# 5_Motors.net
KiCad netlist of a schematic drawn in Altium Designer
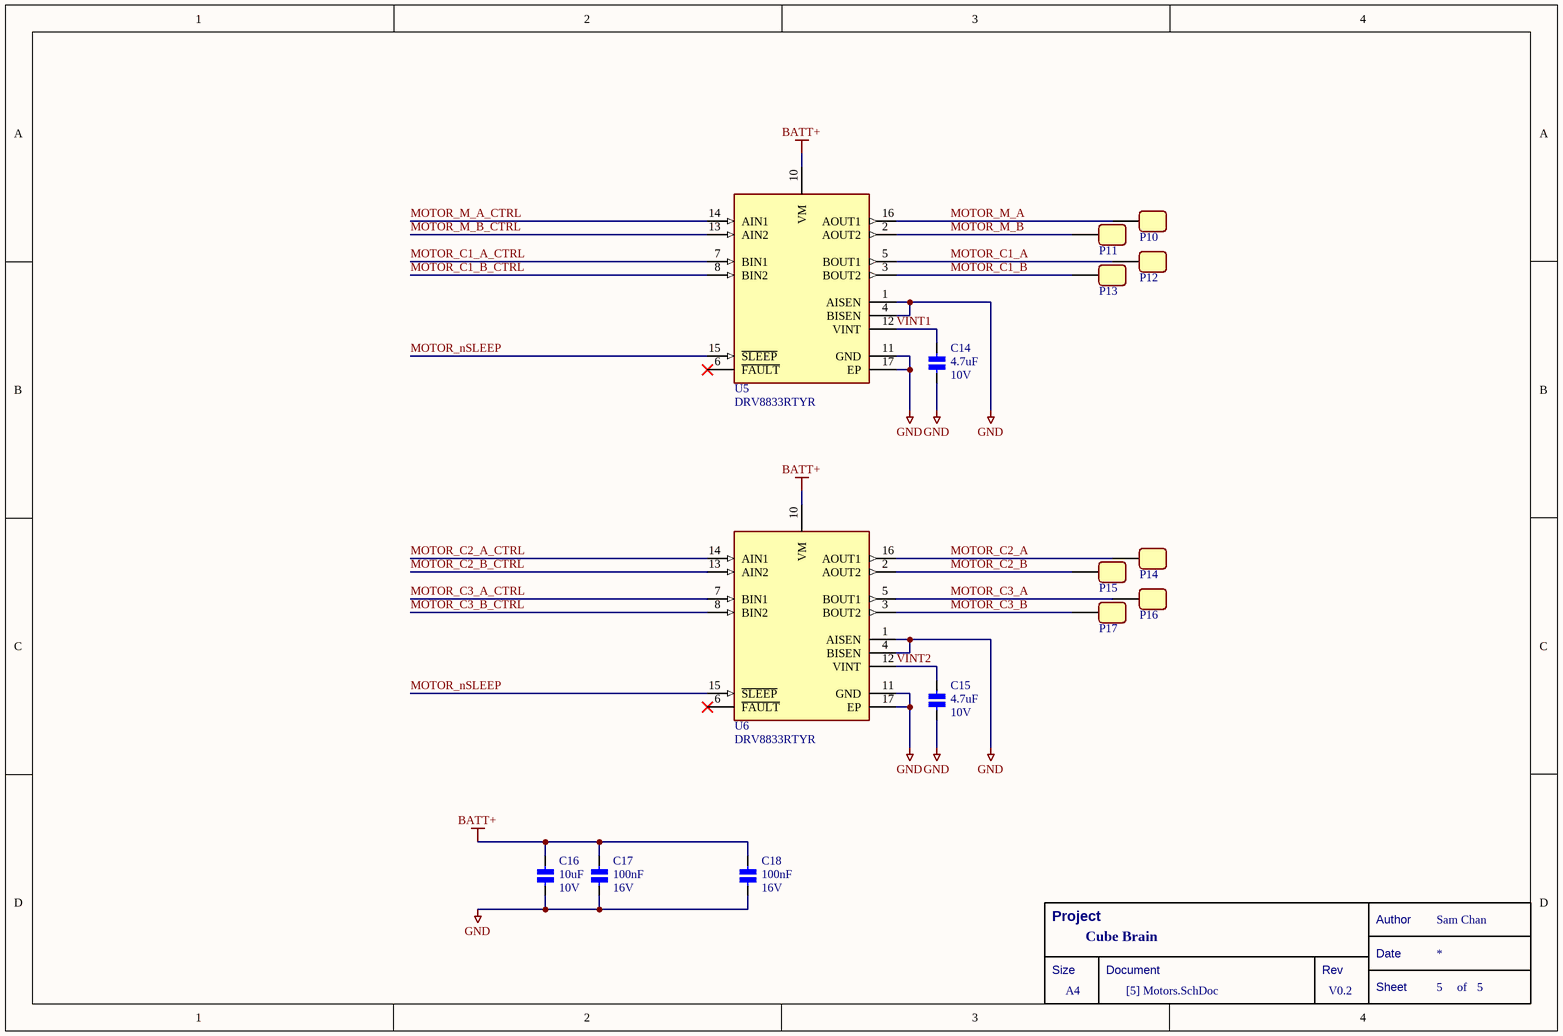
[diagram p0: [5] Motors.SchDoc]

(export (version "E")
  (design (tool "Eeschema 10.0.6"))
  (components
    (comp (ref "C14")
      (value "4.7uF")
      (footprint "CAPC0402X05N")
      (description "CAP CER 4.7UF 10V X5R 0402")
      (fields
        (field (name "MANUFACTURER") "Samsung Electro-Mechanics")
        (field (name "MANUFACTURER PART NUMBER") "CL05A475MP5NRNC")
        (field (name "CAPACITANCE") "4.7uF")
        (field (name "VOLTAGE - RATED") "10V")
      )
      (libsource (lib "Cube Library") (part "CER 4.7UF 10V"))
    )
    (comp (ref "C15")
      (value "4.7uF")
      (footprint "CAPC0402X05N")
      (description "CAP CER 4.7UF 10V X5R 0402")
      (fields
        (field (name "MANUFACTURER") "Samsung Electro-Mechanics")
        (field (name "MANUFACTURER PART NUMBER") "CL05A475MP5NRNC")
        (field (name "CAPACITANCE") "4.7uF")
        (field (name "VOLTAGE - RATED") "10V")
      )
      (libsource (lib "Cube Library") (part "CER 4.7UF 10V"))
    )
    (comp (ref "C16")
      (value "10uF")
      (footprint "CAPC0402X05N")
      (description "CAP CER 10UF 10V X5R 0402")
      (fields
        (field (name "MANUFACTURER") "Murata Electronics")
        (field (name "MANUFACTURER PART NUMBER") "GRM155R61A106ME44D")
        (field (name "CAPACITANCE") "10uF")
        (field (name "VOLTAGE - RATED") "10V")
      )
      (libsource (lib "Cube Library") (part "CER 10UF 10V"))
    )
    (comp (ref "C17")
      (value "100nF")
      (footprint "CAPC0402X05N")
      (description "CAP CER 0.1UF 16V X7R 0402")
      (fields
        (field (name "MANUFACTURER") "Samsung Electro-Mechanics")
        (field (name "MANUFACTURER PART NUMBER") "CL05B104KO5NNNC")
        (field (name "CAPACITANCE") "100nF")
        (field (name "VOLTAGE - RATED") "16V")
      )
      (libsource (lib "Cube Library") (part "CER 100NF 16V"))
    )
    (comp (ref "C18")
      (value "100nF")
      (footprint "CAPC0402X05N")
      (description "CAP CER 0.1UF 16V X7R 0402")
      (fields
        (field (name "MANUFACTURER") "Samsung Electro-Mechanics")
        (field (name "MANUFACTURER PART NUMBER") "CL05B104KO5NNNC")
        (field (name "CAPACITANCE") "100nF")
        (field (name "VOLTAGE - RATED") "16V")
      )
      (libsource (lib "Cube Library") (part "CER 100NF 16V"))
    )
    (comp (ref "P10")
      (value "PAD_4")
      (footprint "PAD_B2B")
      (description "a Pad for board to board connection")
      (libsource (lib "Cube Library") (part "PAD_4"))
    )
    (comp (ref "P11")
      (value "PAD_4")
      (footprint "PAD_B2B")
      (description "a Pad for board to board connection")
      (libsource (lib "Cube Library") (part "PAD_4"))
    )
    (comp (ref "P12")
      (value "PAD_4")
      (footprint "PAD_B2B")
      (description "a Pad for board to board connection")
      (libsource (lib "Cube Library") (part "PAD_4"))
    )
    (comp (ref "P13")
      (value "PAD_4")
      (footprint "PAD_B2B")
      (description "a Pad for board to board connection")
      (libsource (lib "Cube Library") (part "PAD_4"))
    )
    (comp (ref "P14")
      (value "PAD_4")
      (footprint "PAD_B2B")
      (description "a Pad for board to board connection")
      (libsource (lib "Cube Library") (part "PAD_4"))
    )
    (comp (ref "P15")
      (value "PAD_4")
      (footprint "PAD_B2B")
      (description "a Pad for board to board connection")
      (libsource (lib "Cube Library") (part "PAD_4"))
    )
    (comp (ref "P16")
      (value "PAD_4")
      (footprint "PAD_B2B")
      (description "a Pad for board to board connection")
      (libsource (lib "Cube Library") (part "PAD_4"))
    )
    (comp (ref "P17")
      (value "PAD_4")
      (footprint "PAD_B2B")
      (description "a Pad for board to board connection")
      (libsource (lib "Cube Library") (part "PAD_4"))
    )
    (comp (ref "U5")
      (value "DRV8833RTYR")
      (footprint "DRV8833CRTER")
      (description "IC MOTOR DRIVER")
      (fields (field (name "MANUFACTURER") "Texas Instruments"))
      (libsource (lib "Cube Library") (part "DRV8833RTYR"))
    )
    (comp (ref "U6")
      (value "DRV8833RTYR")
      (footprint "DRV8833CRTER")
      (description "IC MOTOR DRIVER")
      (fields (field (name "MANUFACTURER") "Texas Instruments"))
      (libsource (lib "Cube Library") (part "DRV8833RTYR"))
    )
  )
  (nets
    (net (code "1") (name "/MOTOR_C1_A") (class "Default")
      (node (ref "P12") (pin "1") (pinfunction "1_1") (pintype "passive"))
      (node (ref "U5") (pin "5") (pinfunction "BOUT1_5") (pintype "output"))
    )
    (net (code "2") (name "/MOTOR_C1_A_CTRL") (class "Default")
      (node (ref "U5") (pin "7") (pinfunction "BIN1_7") (pintype "input"))
    )
    (net (code "3") (name "/MOTOR_C1_B") (class "Default")
      (node (ref "P13") (pin "1") (pinfunction "1_1") (pintype "passive"))
      (node (ref "U5") (pin "3") (pinfunction "BOUT2_3") (pintype "output"))
    )
    (net (code "4") (name "/MOTOR_C1_B_CTRL") (class "Default")
      (node (ref "U5") (pin "8") (pinfunction "BIN2_8") (pintype "input"))
    )
    (net (code "5") (name "/MOTOR_C2_A") (class "Default")
      (node (ref "P14") (pin "1") (pinfunction "1_1") (pintype "passive"))
      (node (ref "U6") (pin "16") (pinfunction "AOUT1_16") (pintype "output"))
    )
    (net (code "6") (name "/MOTOR_C2_A_CTRL") (class "Default")
      (node (ref "U6") (pin "14") (pinfunction "AIN1_14") (pintype "input"))
    )
    (net (code "7") (name "/MOTOR_C2_B") (class "Default")
      (node (ref "P15") (pin "1") (pinfunction "1_1") (pintype "passive"))
      (node (ref "U6") (pin "2") (pinfunction "AOUT2_2") (pintype "output"))
    )
    (net (code "8") (name "/MOTOR_C2_B_CTRL") (class "Default")
      (node (ref "U6") (pin "13") (pinfunction "AIN2_13") (pintype "input"))
    )
    (net (code "9") (name "/MOTOR_C3_A") (class "Default")
      (node (ref "P16") (pin "1") (pinfunction "1_1") (pintype "passive"))
      (node (ref "U6") (pin "5") (pinfunction "BOUT1_5") (pintype "output"))
    )
    (net (code "10") (name "/MOTOR_C3_A_CTRL") (class "Default")
      (node (ref "U6") (pin "7") (pinfunction "BIN1_7") (pintype "input"))
    )
    (net (code "11") (name "/MOTOR_C3_B") (class "Default")
      (node (ref "P17") (pin "1") (pinfunction "1_1") (pintype "passive"))
      (node (ref "U6") (pin "3") (pinfunction "BOUT2_3") (pintype "output"))
    )
    (net (code "12") (name "/MOTOR_C3_B_CTRL") (class "Default")
      (node (ref "U6") (pin "8") (pinfunction "BIN2_8") (pintype "input"))
    )
    (net (code "13") (name "/MOTOR_M_A") (class "Default")
      (node (ref "P10") (pin "1") (pinfunction "1_1") (pintype "passive"))
      (node (ref "U5") (pin "16") (pinfunction "AOUT1_16") (pintype "output"))
    )
    (net (code "14") (name "/MOTOR_M_A_CTRL") (class "Default")
      (node (ref "U5") (pin "14") (pinfunction "AIN1_14") (pintype "input"))
    )
    (net (code "15") (name "/MOTOR_M_B") (class "Default")
      (node (ref "P11") (pin "1") (pinfunction "1_1") (pintype "passive"))
      (node (ref "U5") (pin "2") (pinfunction "AOUT2_2") (pintype "output"))
    )
    (net (code "16") (name "/MOTOR_M_B_CTRL") (class "Default")
      (node (ref "U5") (pin "13") (pinfunction "AIN2_13") (pintype "input"))
    )
    (net (code "17") (name "/MOTOR_nSLEEP") (class "Default")
      (node (ref "U5") (pin "15") (pinfunction "~{SLEEP}_15") (pintype "input"))
      (node (ref "U6") (pin "15") (pinfunction "~{SLEEP}_15") (pintype "input"))
    )
    (net (code "18") (name "/VINT1") (class "Default")
      (node (ref "C14") (pin "1") (pinfunction "1_1") (pintype "passive"))
      (node (ref "U5") (pin "12") (pinfunction "VINT_12") (pintype "power_in"))
    )
    (net (code "19") (name "/VINT2") (class "Default")
      (node (ref "C15") (pin "1") (pinfunction "1_1") (pintype "passive"))
      (node (ref "U6") (pin "12") (pinfunction "VINT_12") (pintype "power_in"))
    )
    (net (code "20") (name "BATT+") (class "Default")
      (node (ref "C16") (pin "1") (pinfunction "1_1") (pintype "passive"))
      (node (ref "C17") (pin "1") (pinfunction "1_1") (pintype "passive"))
      (node (ref "C18") (pin "1") (pinfunction "1_1") (pintype "passive"))
      (node (ref "U5") (pin "10") (pinfunction "VM_10") (pintype "power_in"))
      (node (ref "U6") (pin "10") (pinfunction "VM_10") (pintype "power_in"))
    )
    (net (code "21") (name "GND") (class "Default")
      (node (ref "C14") (pin "2") (pinfunction "2_2") (pintype "passive"))
      (node (ref "C15") (pin "2") (pinfunction "2_2") (pintype "passive"))
      (node (ref "C16") (pin "2") (pinfunction "2_2") (pintype "passive"))
      (node (ref "C17") (pin "2") (pinfunction "2_2") (pintype "passive"))
      (node (ref "C18") (pin "2") (pinfunction "2_2") (pintype "passive"))
      (node (ref "U5") (pin "1") (pinfunction "AISEN_1") (pintype "passive"))
      (node (ref "U5") (pin "11") (pinfunction "GND_11") (pintype "power_in"))
      (node (ref "U5") (pin "17") (pinfunction "EP_17") (pintype "passive"))
      (node (ref "U5") (pin "4") (pinfunction "BISEN_4") (pintype "passive"))
      (node (ref "U6") (pin "1") (pinfunction "AISEN_1") (pintype "passive"))
      (node (ref "U6") (pin "11") (pinfunction "GND_11") (pintype "power_in"))
      (node (ref "U6") (pin "17") (pinfunction "EP_17") (pintype "passive"))
      (node (ref "U6") (pin "4") (pinfunction "BISEN_4") (pintype "passive"))
    )
    (net (code "22") (name "unconnected-(U5-~{FAULT}-Pad6)") (class "Default")
      (node (ref "U5") (pin "6") (pinfunction "~{FAULT}_6") (pintype "open_collector+no_connect"))
    )
    (net (code "23") (name "unconnected-(U6-~{FAULT}-Pad6)") (class "Default")
      (node (ref "U6") (pin "6") (pinfunction "~{FAULT}_6") (pintype "open_collector+no_connect"))
    )
  )
)
